# 04_REGULATORS.net
KiCad netlist of a schematic drawn in Altium Designer
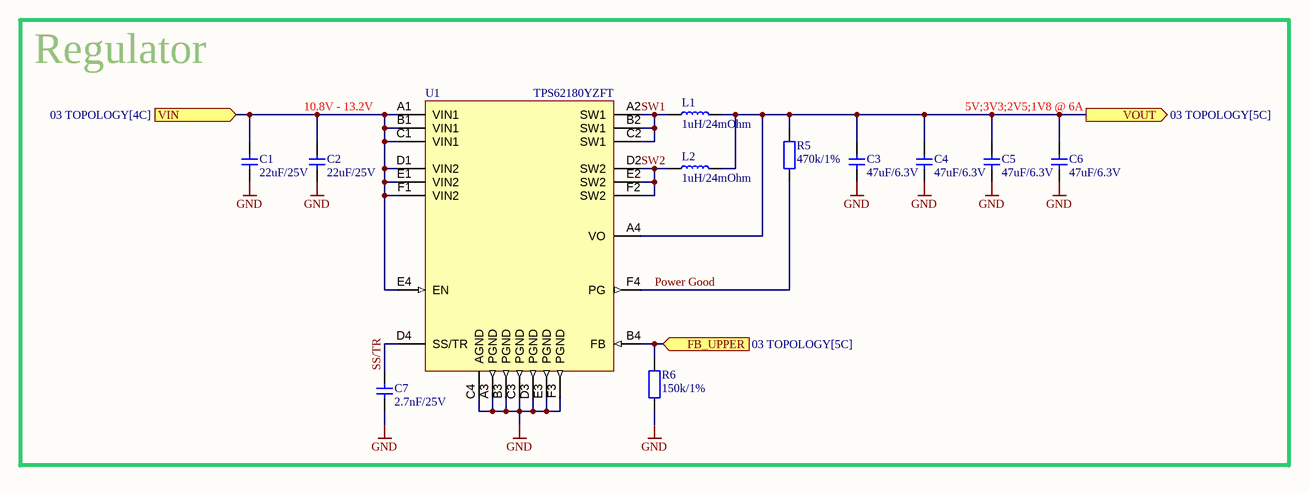
[diagram p0: 04 REGULATORS.SchDoc]

(export (version "E")
  (design (tool "Eeschema 10.0.6"))
  (components
    (comp (ref "C1")
      (value "22uF/25V")
      (footprint "CAPC2012X14M")
      (description "22 µF ±20% 25V Ceramic Capacitor X5R 0805 (2012 Metric)")
      (fields (field (name "MPN") "GRT21BR61E226ME13L"))
      (libsource (lib "PowerModule") (part "GRT21BR61E226ME13L"))
    )
    (comp (ref "C2")
      (value "22uF/25V")
      (footprint "CAPC2012X14M")
      (description "22 µF ±20% 25V Ceramic Capacitor X5R 0805 (2012 Metric)")
      (fields (field (name "MPN") "GRT21BR61E226ME13L"))
      (libsource (lib "PowerModule") (part "GRT21BR61E226ME13L"))
    )
    (comp (ref "C3")
      (value "47uF/6.3V")
      (footprint "CAPC2012X14M")
      (description "47 µF ±20% 6.3V Ceramic Capacitor X5R 0603 (1608 Metric)")
      (fields (field (name "MPN") "GRM188R60J476ME15D"))
      (libsource (lib "PowerModule") (part "GRM188R60J476ME15D"))
    )
    (comp (ref "C4")
      (value "47uF/6.3V")
      (footprint "CAPC2012X14M")
      (description "47 µF ±20% 6.3V Ceramic Capacitor X5R 0603 (1608 Metric)")
      (fields (field (name "MPN") "GRM188R60J476ME15D"))
      (libsource (lib "PowerModule") (part "GRM188R60J476ME15D"))
    )
    (comp (ref "C5")
      (value "47uF/6.3V")
      (footprint "CAPC2012X14M")
      (description "47 µF ±20% 6.3V Ceramic Capacitor X5R 0603 (1608 Metric)")
      (fields (field (name "MPN") "GRM188R60J476ME15D"))
      (libsource (lib "PowerModule") (part "GRM188R60J476ME15D"))
    )
    (comp (ref "C6")
      (value "47uF/6.3V")
      (footprint "CAPC2012X14M")
      (description "47 µF ±20% 6.3V Ceramic Capacitor X5R 0603 (1608 Metric)")
      (fields (field (name "MPN") "GRM188R60J476ME15D"))
      (libsource (lib "PowerModule") (part "GRM188R60J476ME15D"))
    )
    (comp (ref "C7")
      (value "2.7nF/25V")
      (footprint "CAPC1005X07M")
      (description "2700 pF ±10% 25V Ceramic Capacitor X7R 0402 (1005 Metric)")
      (fields (field (name "MPN") "CC0402KRX7R8BB272"))
      (libsource (lib "PowerModule") (part "CC0402KRX7R8BB272"))
    )
    (comp (ref "L1")
      (value "1uH/24mOhm")
      (footprint "INDP3030X20M")
      (description "1 µH Shielded Molded Inductor 5 A 24mOhm Max Nonstandard")
      (fields (field (name "MPN") "IHLP1212BZER1R0M11"))
      (libsource (lib "PowerModule") (part "IHLP1212BZER1R0M11"))
    )
    (comp (ref "L2")
      (value "1uH/24mOhm")
      (footprint "INDP3030X20M")
      (description "1 µH Shielded Molded Inductor 5 A 24mOhm Max Nonstandard")
      (fields (field (name "MPN") "IHLP1212BZER1R0M11"))
      (libsource (lib "PowerModule") (part "IHLP1212BZER1R0M11"))
    )
    (comp (ref "R5")
      (value "470k/1%")
      (footprint "RESC1005X04M")
      (description "470 kOhms ±1% 0.063W, 1/16W Chip Resistor 0402 (1005 Metric) Automotive AEC-Q200 Thick Film")
      (fields (field (name "MPN") "RMCF0402FT470K"))
      (libsource (lib "PowerModule") (part "CRCW0402787KFKED_1RMCF0402FT470K"))
    )
    (comp (ref "R6")
      (value "150k/1%")
      (footprint "RESC1005X04M")
      (description "150 kOhms ±1% 0.063W, 1/16W Chip Resistor 0402 (1005 Metric) Automotive AEC-Q200 Thick Film")
      (fields (field (name "MPN") "CRCW0402150KFKED"))
      (libsource (lib "PowerModule") (part "CRCW0402150KFKED"))
    )
    (comp (ref "U1")
      (value "TPS62180YZFT")
      (footprint "BGA24C50P4X6_210X310X62")
      (description "Buck Switching Regulator IC Positive Adjustable 0.9V 1 Output 6A 24-UFBGA, DSBGA")
      (libsource (lib "PowerModule") (part "TPS62180YZFT"))
    )
  )
  (nets
    (net (code "1") (name "/FB_UPPER") (class "Default")
      (node (ref "R6") (pin "2") (pinfunction "2_2") (pintype "passive"))
      (node (ref "U1") (pin "B4") (pinfunction "FB_B4") (pintype "input"))
    )
    (net (code "2") (name "/Power Good") (class "Default")
      (node (ref "R5") (pin "1") (pinfunction "1_1") (pintype "passive"))
      (node (ref "U1") (pin "F4") (pinfunction "PG_F4") (pintype "output"))
    )
    (net (code "3") (name "/SS{slash}TR") (class "Default")
      (node (ref "C7") (pin "2") (pinfunction "2_2") (pintype "passive"))
      (node (ref "U1") (pin "D4") (pinfunction "SS/TR_D4") (pintype "passive"))
    )
    (net (code "4") (name "/SW1") (class "Default")
      (node (ref "L1") (pin "1") (pinfunction "1_1") (pintype "passive"))
      (node (ref "U1") (pin "A2") (pinfunction "SW1_A2") (pintype "power_in"))
      (node (ref "U1") (pin "B2") (pinfunction "SW1_B2") (pintype "passive"))
      (node (ref "U1") (pin "C2") (pinfunction "SW1_C2") (pintype "passive"))
    )
    (net (code "5") (name "/SW2") (class "Default")
      (node (ref "L2") (pin "1") (pinfunction "1_1") (pintype "passive"))
      (node (ref "U1") (pin "D2") (pinfunction "SW2_D2") (pintype "passive"))
      (node (ref "U1") (pin "E2") (pinfunction "SW2_E2") (pintype "passive"))
      (node (ref "U1") (pin "F2") (pinfunction "SW2_F2") (pintype "passive"))
    )
    (net (code "6") (name "/VIN") (class "Default")
      (node (ref "C1") (pin "2") (pinfunction "2_2") (pintype "passive"))
      (node (ref "C2") (pin "2") (pinfunction "2_2") (pintype "passive"))
      (node (ref "U1") (pin "A1") (pinfunction "VIN1_A1") (pintype "passive"))
      (node (ref "U1") (pin "B1") (pinfunction "VIN1_B1") (pintype "passive"))
      (node (ref "U1") (pin "C1") (pinfunction "VIN1_C1") (pintype "passive"))
      (node (ref "U1") (pin "D1") (pinfunction "VIN2_D1") (pintype "passive"))
      (node (ref "U1") (pin "E1") (pinfunction "VIN2_E1") (pintype "passive"))
      (node (ref "U1") (pin "E4") (pinfunction "EN_E4") (pintype "input"))
      (node (ref "U1") (pin "F1") (pinfunction "VIN2_F1") (pintype "passive"))
    )
    (net (code "7") (name "/VOUT") (class "Default")
      (node (ref "C3") (pin "2") (pinfunction "2_2") (pintype "passive"))
      (node (ref "C4") (pin "2") (pinfunction "2_2") (pintype "passive"))
      (node (ref "C5") (pin "2") (pinfunction "2_2") (pintype "passive"))
      (node (ref "C6") (pin "2") (pinfunction "2_2") (pintype "passive"))
      (node (ref "L1") (pin "2") (pinfunction "2_2") (pintype "passive"))
      (node (ref "L2") (pin "2") (pinfunction "2_2") (pintype "passive"))
      (node (ref "R5") (pin "2") (pinfunction "2_2") (pintype "passive"))
      (node (ref "U1") (pin "A4") (pinfunction "VO_A4") (pintype "passive"))
    )
    (net (code "8") (name "GND") (class "Default")
      (node (ref "C1") (pin "1") (pinfunction "1_1") (pintype "passive"))
      (node (ref "C2") (pin "1") (pinfunction "1_1") (pintype "passive"))
      (node (ref "C3") (pin "1") (pinfunction "1_1") (pintype "passive"))
      (node (ref "C4") (pin "1") (pinfunction "1_1") (pintype "passive"))
      (node (ref "C5") (pin "1") (pinfunction "1_1") (pintype "passive"))
      (node (ref "C6") (pin "1") (pinfunction "1_1") (pintype "passive"))
      (node (ref "C7") (pin "1") (pinfunction "1_1") (pintype "passive"))
      (node (ref "R6") (pin "1") (pinfunction "1_1") (pintype "passive"))
      (node (ref "U1") (pin "A3") (pinfunction "PGND_A3") (pintype "output"))
      (node (ref "U1") (pin "B3") (pinfunction "PGND_B3") (pintype "output"))
      (node (ref "U1") (pin "C3") (pinfunction "PGND_C3") (pintype "output"))
      (node (ref "U1") (pin "C4") (pinfunction "AGND_C4") (pintype "power_in"))
      (node (ref "U1") (pin "D3") (pinfunction "PGND_D3") (pintype "output"))
      (node (ref "U1") (pin "E3") (pinfunction "PGND_E3") (pintype "output"))
      (node (ref "U1") (pin "F3") (pinfunction "PGND_F3") (pintype "output"))
    )
  )
)
